# CON-USB.net
KiCad netlist of a schematic drawn in Altium Designer
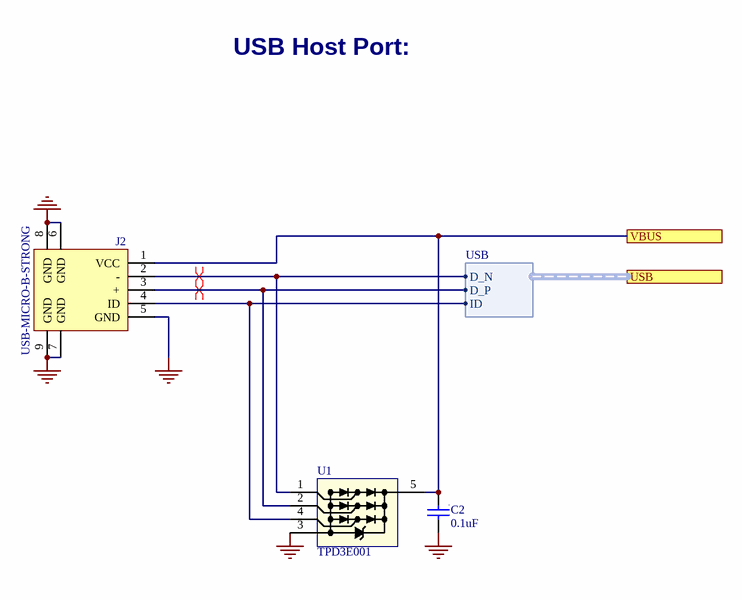
[diagram p0: CON-USB.SchDoc]

(export (version "E")
  (design (tool "Eeschema 10.0.6"))
  (components
    (comp (ref "C2")
      (value "0.1uF")
      (footprint "0402")
      (description "CAP CER .10UF 50V X7R 10% 0402")
      (fields
        (field (name "MANUFACTURER") "TDK Corporation")
        (field (name "MANUFACTURER PART NUMBER") "C1005X7R1H104K")
        (field (name "PUBLISHER") "Altium Limited")
      )
      (libsource (lib "General") (part "Cap"))
    )
    (comp (ref "J2")
      (value "USB-MICRO-B-STRONG")
      (footprint "USB Micro AB R/A THR - design")
      (description "CONN USB MICRO B RECPT SMT R/A")
      (fields
        (field (name "MANUFACTURER") "Amphenol FCI")
        (field (name "MANUFACTURER PART NUMBER") "10118194-0001LF")
      )
      (libsource (lib "Connectors") (part "USB-TYPEAB-4GND"))
    )
    (comp (ref "U1")
      (value "TPD3E001")
      (footprint "SOTFL50P160X60-5N")
      (description "TVS DIODE 5.5V SOT5")
      (fields
        (field (name "MANUFACTURER") "Texas Instruments")
        (field (name "MANUFACTURER PART NUMBER") "TPD3E001DRLR")
      )
      (libsource (lib "ICs") (part "TPD3E001"))
    )
  )
  (nets
    (net (code "2") (name "/VBUS") (class "Default")
      (node (ref "C2") (pin "1") (pinfunction "1_1") (pintype "passive"))
      (node (ref "J2") (pin "1") (pinfunction "VCC_1") (pintype "passive"))
      (node (ref "U1") (pin "5") (pinfunction "nc_5") (pintype "passive"))
    )
    (net (code "4") (name "GND") (class "Default")
      (node (ref "C2") (pin "2") (pinfunction "2_2") (pintype "passive"))
      (node (ref "J2") (pin "5") (pinfunction "GND_5") (pintype "passive"))
      (node (ref "J2") (pin "6") (pinfunction "GND_6") (pintype "passive"))
      (node (ref "J2") (pin "7") (pinfunction "GND_7") (pintype "passive"))
      (node (ref "J2") (pin "8") (pinfunction "GND_8") (pintype "passive"))
      (node (ref "J2") (pin "9") (pinfunction "GND_9") (pintype "passive"))
      (node (ref "U1") (pin "3") (pintype "passive"))
    )
    (net (code "5") (name "Net-(J2-+)") (class "Default")
      (node (ref "J2") (pin "3") (pinfunction "+_3") (pintype "passive"))
      (node (ref "U1") (pin "2") (pintype "passive"))
    )
    (net (code "6") (name "Net-(J2--)") (class "Default")
      (node (ref "J2") (pin "2") (pinfunction "-_2") (pintype "passive"))
      (node (ref "U1") (pin "1") (pintype "passive"))
    )
    (net (code "7") (name "Net-(J2-ID)") (class "Default")
      (node (ref "J2") (pin "4") (pinfunction "ID_4") (pintype "passive"))
      (node (ref "U1") (pin "4") (pinfunction "nc_4") (pintype "passive"))
    )
  )
)
